# 01_DDR3L_256Mx32bits.net
KiCad netlist of a schematic drawn in Altium Designer
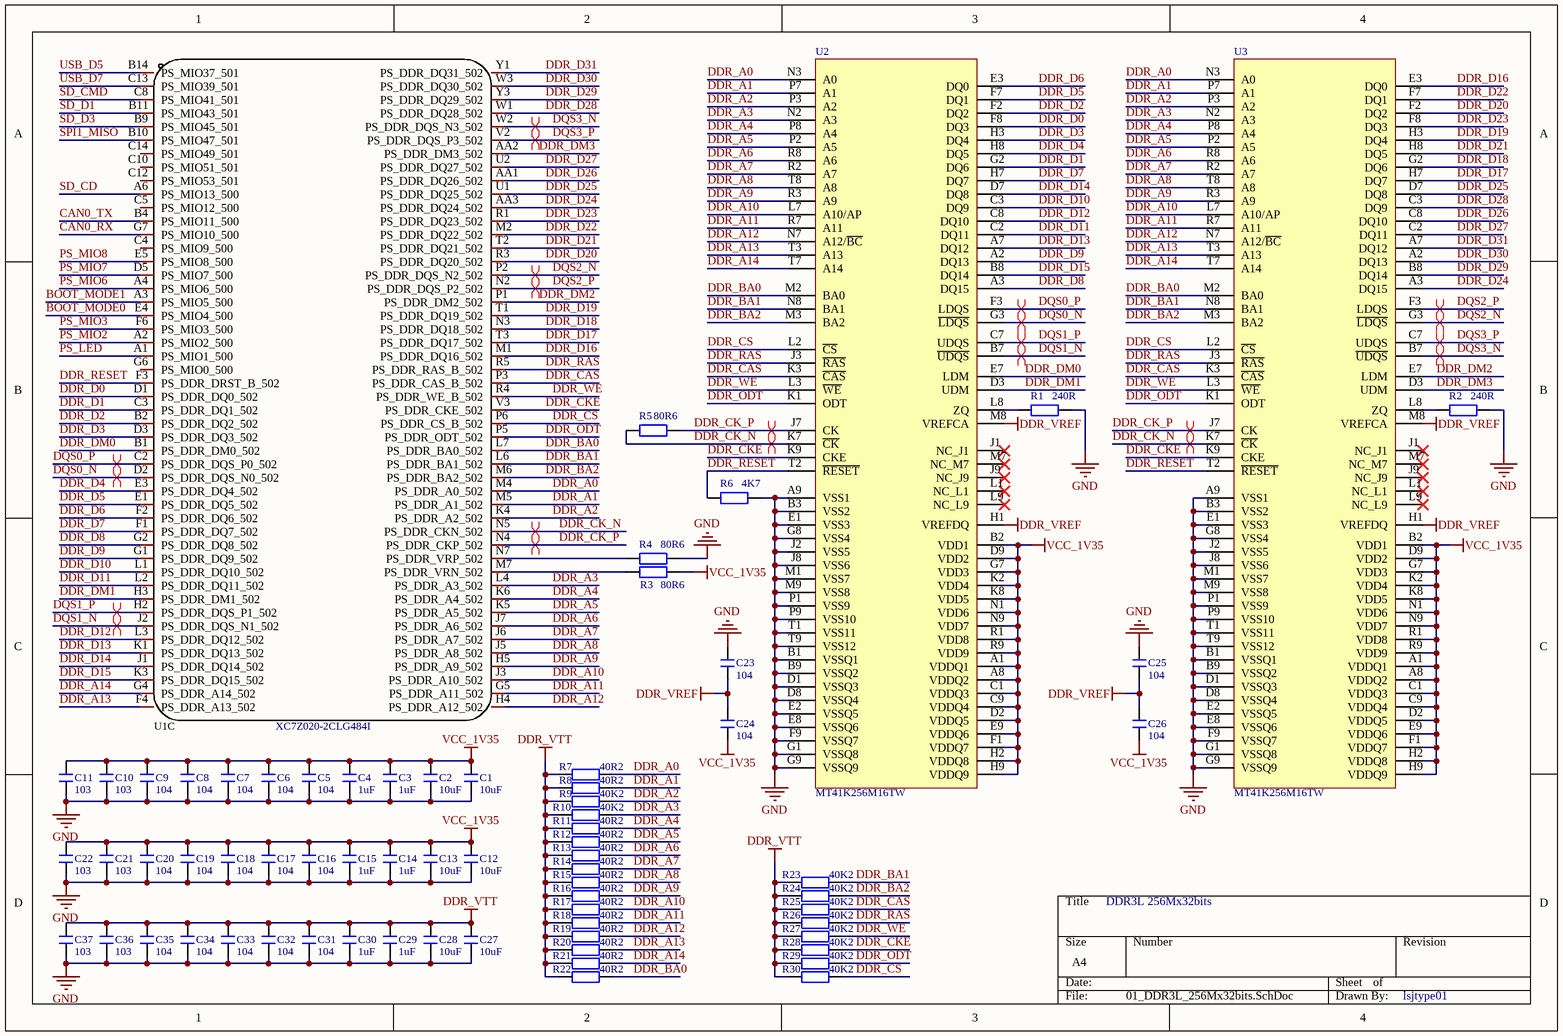
[diagram p0: 01_DDR3L_256Mx32bits.SchDoc]

(export (version "E")
  (design (tool "Eeschema 10.0.6"))
  (components
    (comp (ref "C1")
      (value "10uF")
      (footprint "C 0603")
      (description "无极性贴片电容")
      (fields (field (name "版权归属") "源创客"))
      (libsource (lib "STM32MP157核心板封装库V1.2") (part "C"))
    )
    (comp (ref "C2")
      (value "10uF")
      (footprint "C 0603")
      (description "无极性贴片电容")
      (fields (field (name "版权归属") "源创客"))
      (libsource (lib "STM32MP157核心板封装库V1.2") (part "C"))
    )
    (comp (ref "C3")
      (value "1uF")
      (footprint "C 0402")
      (description "无极性贴片电容")
      (fields (field (name "版权归属") "源创客"))
      (libsource (lib "STM32MP157核心板封装库V1.2") (part "C"))
    )
    (comp (ref "C4")
      (value "1uF")
      (footprint "C 0402")
      (description "无极性贴片电容")
      (fields (field (name "版权归属") "源创客"))
      (libsource (lib "STM32MP157核心板封装库V1.2") (part "C"))
    )
    (comp (ref "C5")
      (value "104")
      (footprint "C 0402")
      (description "无极性贴片电容")
      (fields (field (name "版权归属") "源创客"))
      (libsource (lib "STM32MP157核心板封装库V1.2") (part "C"))
    )
    (comp (ref "C6")
      (value "104")
      (footprint "C 0402")
      (description "无极性贴片电容")
      (fields (field (name "版权归属") "源创客"))
      (libsource (lib "STM32MP157核心板封装库V1.2") (part "C"))
    )
    (comp (ref "C7")
      (value "104")
      (footprint "C 0402")
      (description "无极性贴片电容")
      (fields (field (name "版权归属") "源创客"))
      (libsource (lib "STM32MP157核心板封装库V1.2") (part "C"))
    )
    (comp (ref "C8")
      (value "104")
      (footprint "C 0402")
      (description "无极性贴片电容")
      (fields (field (name "版权归属") "源创客"))
      (libsource (lib "STM32MP157核心板封装库V1.2") (part "C"))
    )
    (comp (ref "C9")
      (value "104")
      (footprint "C 0402")
      (description "无极性贴片电容")
      (fields (field (name "版权归属") "源创客"))
      (libsource (lib "STM32MP157核心板封装库V1.2") (part "C"))
    )
    (comp (ref "C10")
      (value "103")
      (footprint "C 0402")
      (description "无极性贴片电容")
      (fields (field (name "版权归属") "源创客"))
      (libsource (lib "STM32MP157核心板封装库V1.2") (part "C"))
    )
    (comp (ref "C11")
      (value "103")
      (footprint "C 0402")
      (description "无极性贴片电容")
      (fields (field (name "版权归属") "源创客"))
      (libsource (lib "STM32MP157核心板封装库V1.2") (part "C"))
    )
    (comp (ref "C12")
      (value "10uF")
      (footprint "C 0603")
      (description "无极性贴片电容")
      (fields (field (name "版权归属") "源创客"))
      (libsource (lib "STM32MP157核心板封装库V1.2") (part "C"))
    )
    (comp (ref "C13")
      (value "10uF")
      (footprint "C 0603")
      (description "无极性贴片电容")
      (fields (field (name "版权归属") "源创客"))
      (libsource (lib "STM32MP157核心板封装库V1.2") (part "C"))
    )
    (comp (ref "C14")
      (value "1uF")
      (footprint "C 0402")
      (description "无极性贴片电容")
      (fields (field (name "版权归属") "源创客"))
      (libsource (lib "STM32MP157核心板封装库V1.2") (part "C"))
    )
    (comp (ref "C15")
      (value "1uF")
      (footprint "C 0402")
      (description "无极性贴片电容")
      (fields (field (name "版权归属") "源创客"))
      (libsource (lib "STM32MP157核心板封装库V1.2") (part "C"))
    )
    (comp (ref "C16")
      (value "104")
      (footprint "C 0402")
      (description "无极性贴片电容")
      (fields (field (name "版权归属") "源创客"))
      (libsource (lib "STM32MP157核心板封装库V1.2") (part "C"))
    )
    (comp (ref "C17")
      (value "104")
      (footprint "C 0402")
      (description "无极性贴片电容")
      (fields (field (name "版权归属") "源创客"))
      (libsource (lib "STM32MP157核心板封装库V1.2") (part "C"))
    )
    (comp (ref "C18")
      (value "104")
      (footprint "C 0402")
      (description "无极性贴片电容")
      (fields (field (name "版权归属") "源创客"))
      (libsource (lib "STM32MP157核心板封装库V1.2") (part "C"))
    )
    (comp (ref "C19")
      (value "104")
      (footprint "C 0402")
      (description "无极性贴片电容")
      (fields (field (name "版权归属") "源创客"))
      (libsource (lib "STM32MP157核心板封装库V1.2") (part "C"))
    )
    (comp (ref "C20")
      (value "104")
      (footprint "C 0402")
      (description "无极性贴片电容")
      (fields (field (name "版权归属") "源创客"))
      (libsource (lib "STM32MP157核心板封装库V1.2") (part "C"))
    )
    (comp (ref "C21")
      (value "103")
      (footprint "C 0402")
      (description "无极性贴片电容")
      (fields (field (name "版权归属") "源创客"))
      (libsource (lib "STM32MP157核心板封装库V1.2") (part "C"))
    )
    (comp (ref "C22")
      (value "103")
      (footprint "C 0402")
      (description "无极性贴片电容")
      (fields (field (name "版权归属") "源创客"))
      (libsource (lib "STM32MP157核心板封装库V1.2") (part "C"))
    )
    (comp (ref "C23")
      (value "104")
      (footprint "C 0402")
      (description "无极性贴片电容")
      (fields (field (name "版权归属") "源创客"))
      (libsource (lib "STM32MP157核心板封装库V1.2") (part "C"))
    )
    (comp (ref "C24")
      (value "104")
      (footprint "C 0402")
      (description "无极性贴片电容")
      (fields (field (name "版权归属") "源创客"))
      (libsource (lib "STM32MP157核心板封装库V1.2") (part "C"))
    )
    (comp (ref "C25")
      (value "104")
      (footprint "C 0402")
      (description "无极性贴片电容")
      (fields (field (name "版权归属") "源创客"))
      (libsource (lib "STM32MP157核心板封装库V1.2") (part "C"))
    )
    (comp (ref "C26")
      (value "104")
      (footprint "C 0402")
      (description "无极性贴片电容")
      (fields (field (name "版权归属") "源创客"))
      (libsource (lib "STM32MP157核心板封装库V1.2") (part "C"))
    )
    (comp (ref "C27")
      (value "10uF")
      (footprint "C 0603")
      (description "无极性贴片电容")
      (fields (field (name "版权归属") "源创客"))
      (libsource (lib "STM32MP157核心板封装库V1.2") (part "C"))
    )
    (comp (ref "C28")
      (value "10uF")
      (footprint "C 0603")
      (description "无极性贴片电容")
      (fields (field (name "版权归属") "源创客"))
      (libsource (lib "STM32MP157核心板封装库V1.2") (part "C"))
    )
    (comp (ref "C29")
      (value "1uF")
      (footprint "C 0402")
      (description "无极性贴片电容")
      (fields (field (name "版权归属") "源创客"))
      (libsource (lib "STM32MP157核心板封装库V1.2") (part "C"))
    )
    (comp (ref "C30")
      (value "1uF")
      (footprint "C 0402")
      (description "无极性贴片电容")
      (fields (field (name "版权归属") "源创客"))
      (libsource (lib "STM32MP157核心板封装库V1.2") (part "C"))
    )
    (comp (ref "C31")
      (value "104")
      (footprint "C 0402")
      (description "无极性贴片电容")
      (fields (field (name "版权归属") "源创客"))
      (libsource (lib "STM32MP157核心板封装库V1.2") (part "C"))
    )
    (comp (ref "C32")
      (value "104")
      (footprint "C 0402")
      (description "无极性贴片电容")
      (fields (field (name "版权归属") "源创客"))
      (libsource (lib "STM32MP157核心板封装库V1.2") (part "C"))
    )
    (comp (ref "C33")
      (value "104")
      (footprint "C 0402")
      (description "无极性贴片电容")
      (fields (field (name "版权归属") "源创客"))
      (libsource (lib "STM32MP157核心板封装库V1.2") (part "C"))
    )
    (comp (ref "C34")
      (value "104")
      (footprint "C 0402")
      (description "无极性贴片电容")
      (fields (field (name "版权归属") "源创客"))
      (libsource (lib "STM32MP157核心板封装库V1.2") (part "C"))
    )
    (comp (ref "C35")
      (value "104")
      (footprint "C 0402")
      (description "无极性贴片电容")
      (fields (field (name "版权归属") "源创客"))
      (libsource (lib "STM32MP157核心板封装库V1.2") (part "C"))
    )
    (comp (ref "C36")
      (value "103")
      (footprint "C 0402")
      (description "无极性贴片电容")
      (fields (field (name "版权归属") "源创客"))
      (libsource (lib "STM32MP157核心板封装库V1.2") (part "C"))
    )
    (comp (ref "C37")
      (value "103")
      (footprint "C 0402")
      (description "无极性贴片电容")
      (fields (field (name "版权归属") "源创客"))
      (libsource (lib "STM32MP157核心板封装库V1.2") (part "C"))
    )
    (comp (ref "R1")
      (value "240R")
      (footprint "R 0402")
      (description "贴片电阻")
      (fields (field (name "版权归属") "源创客"))
      (libsource (lib "STM32MP157核心板封装库V1.2") (part "R"))
    )
    (comp (ref "R2")
      (value "240R")
      (footprint "R 0402")
      (description "贴片电阻")
      (fields (field (name "版权归属") "源创客"))
      (libsource (lib "STM32MP157核心板封装库V1.2") (part "R"))
    )
    (comp (ref "R3")
      (value "80R6")
      (footprint "R 0402")
      (description "贴片电阻")
      (fields (field (name "版权归属") "源创客"))
      (libsource (lib "STM32MP157核心板封装库V1.2") (part "R"))
    )
    (comp (ref "R4")
      (value "80R6")
      (footprint "R 0402")
      (description "贴片电阻")
      (fields (field (name "版权归属") "源创客"))
      (libsource (lib "STM32MP157核心板封装库V1.2") (part "R"))
    )
    (comp (ref "R5")
      (value "80R6")
      (footprint "R 0402")
      (description "贴片电阻")
      (fields (field (name "版权归属") "源创客"))
      (libsource (lib "STM32MP157核心板封装库V1.2") (part "R"))
    )
    (comp (ref "R6")
      (value "4K7")
      (footprint "R 0402")
      (description "贴片电阻")
      (fields (field (name "版权归属") "源创客"))
      (libsource (lib "STM32MP157核心板封装库V1.2") (part "R"))
    )
    (comp (ref "R7")
      (value "40R2")
      (footprint "R 0402")
      (description "贴片电阻")
      (fields (field (name "版权归属") "源创客"))
      (libsource (lib "STM32MP157核心板封装库V1.2") (part "R"))
    )
    (comp (ref "R8")
      (value "40R2")
      (footprint "R 0402")
      (description "贴片电阻")
      (fields (field (name "版权归属") "源创客"))
      (libsource (lib "STM32MP157核心板封装库V1.2") (part "R"))
    )
    (comp (ref "R9")
      (value "40K2")
      (footprint "R 0402")
      (description "贴片电阻")
      (fields (field (name "版权归属") "源创客"))
      (libsource (lib "STM32MP157核心板封装库V1.2") (part "R"))
    )
    (comp (ref "R10")
      (value "40K2")
      (footprint "R 0402")
      (description "贴片电阻")
      (fields (field (name "版权归属") "源创客"))
      (libsource (lib "STM32MP157核心板封装库V1.2") (part "R"))
    )
    (comp (ref "R11")
      (value "40R2")
      (footprint "R 0402")
      (description "贴片电阻")
      (fields (field (name "版权归属") "源创客"))
      (libsource (lib "STM32MP157核心板封装库V1.2") (part "R"))
    )
    (comp (ref "R12")
      (value "40R2")
      (footprint "R 0402")
      (description "贴片电阻")
      (fields (field (name "版权归属") "源创客"))
      (libsource (lib "STM32MP157核心板封装库V1.2") (part "R"))
    )
    (comp (ref "R13")
      (value "40R2")
      (footprint "R 0402")
      (description "贴片电阻")
      (fields (field (name "版权归属") "源创客"))
      (libsource (lib "STM32MP157核心板封装库V1.2") (part "R"))
    )
    (comp (ref "R14")
      (value "40R2")
      (footprint "R 0402")
      (description "贴片电阻")
      (fields (field (name "版权归属") "源创客"))
      (libsource (lib "STM32MP157核心板封装库V1.2") (part "R"))
    )
    (comp (ref "R15")
      (value "40R2")
      (footprint "R 0402")
      (description "贴片电阻")
      (fields (field (name "版权归属") "源创客"))
      (libsource (lib "STM32MP157核心板封装库V1.2") (part "R"))
    )
    (comp (ref "R16")
      (value "40R2")
      (footprint "R 0402")
      (description "贴片电阻")
      (fields (field (name "版权归属") "源创客"))
      (libsource (lib "STM32MP157核心板封装库V1.2") (part "R"))
    )
    (comp (ref "R17")
      (value "40R2")
      (footprint "R 0402")
      (description "贴片电阻")
      (fields (field (name "版权归属") "源创客"))
      (libsource (lib "STM32MP157核心板封装库V1.2") (part "R"))
    )
    (comp (ref "R18")
      (value "40R2")
      (footprint "R 0402")
      (description "贴片电阻")
      (fields (field (name "版权归属") "源创客"))
      (libsource (lib "STM32MP157核心板封装库V1.2") (part "R"))
    )
    (comp (ref "R19")
      (value "40R2")
      (footprint "R 0402")
      (description "贴片电阻")
      (fields (field (name "版权归属") "源创客"))
      (libsource (lib "STM32MP157核心板封装库V1.2") (part "R"))
    )
    (comp (ref "R20")
      (value "40R2")
      (footprint "R 0402")
      (description "贴片电阻")
      (fields (field (name "版权归属") "源创客"))
      (libsource (lib "STM32MP157核心板封装库V1.2") (part "R"))
    )
    (comp (ref "R21")
      (value "40R2")
      (footprint "R 0402")
      (description "贴片电阻")
      (fields (field (name "版权归属") "源创客"))
      (libsource (lib "STM32MP157核心板封装库V1.2") (part "R"))
    )
    (comp (ref "R22")
      (value "40R2")
      (footprint "R 0402")
      (description "贴片电阻")
      (fields (field (name "版权归属") "源创客"))
      (libsource (lib "STM32MP157核心板封装库V1.2") (part "R"))
    )
    (comp (ref "R23")
      (value "40K2")
      (footprint "R 0402")
      (description "贴片电阻")
      (fields (field (name "版权归属") "源创客"))
      (libsource (lib "STM32MP157核心板封装库V1.2") (part "R"))
    )
    (comp (ref "R24")
      (value "40K2")
      (footprint "R 0402")
      (description "贴片电阻")
      (fields (field (name "版权归属") "源创客"))
      (libsource (lib "STM32MP157核心板封装库V1.2") (part "R"))
    )
    (comp (ref "R25")
      (value "40K2")
      (footprint "R 0402")
      (description "贴片电阻")
      (fields (field (name "版权归属") "源创客"))
      (libsource (lib "STM32MP157核心板封装库V1.2") (part "R"))
    )
    (comp (ref "R26")
      (value "40K2")
      (footprint "R 0402")
      (description "贴片电阻")
      (fields (field (name "版权归属") "源创客"))
      (libsource (lib "STM32MP157核心板封装库V1.2") (part "R"))
    )
    (comp (ref "R27")
      (value "40K2")
      (footprint "R 0402")
      (description "贴片电阻")
      (fields (field (name "版权归属") "源创客"))
      (libsource (lib "STM32MP157核心板封装库V1.2") (part "R"))
    )
    (comp (ref "R28")
      (value "40K2")
      (footprint "R 0402")
      (description "贴片电阻")
      (fields (field (name "版权归属") "源创客"))
      (libsource (lib "STM32MP157核心板封装库V1.2") (part "R"))
    )
    (comp (ref "R29")
      (value "40K2")
      (footprint "R 0402")
      (description "贴片电阻")
      (fields (field (name "版权归属") "源创客"))
      (libsource (lib "STM32MP157核心板封装库V1.2") (part "R"))
    )
    (comp (ref "R30")
      (value "40K2")
      (footprint "R 0402")
      (description "贴片电阻")
      (fields (field (name "版权归属") "源创客"))
      (libsource (lib "STM32MP157核心板封装库V1.2") (part "R"))
    )
    (comp (ref "U1")
      (value "XC7Z020-2CLG484I")
      (footprint "CSPBGA-484")
      (fields (field (name "MANUFACTURER") "XILINX(赛灵思)"))
      (libsource (lib "XC7Z020-2CLG484I1") (part "XC7Z020-2CLG484I"))
    )
    (comp (ref "U2")
      (value "MT41K256M16TW")
      (footprint "FBGA_96")
      (libsource (lib "STM32MP157核心板封装库V1.2") (part "MT41K256M16TW"))
    )
    (comp (ref "U3")
      (value "MT41K256M16TW")
      (footprint "FBGA_96")
      (libsource (lib "STM32MP157核心板封装库V1.2") (part "MT41K256M16TW"))
    )
  )
  (nets
    (net (code "1") (name "/BOOT_MODE0") (class "Default")
      (node (ref "U1") (pin "E4") (pinfunction "PS_MIO4_500_E4") (pintype "passive"))
    )
    (net (code "2") (name "/BOOT_MODE1") (class "Default")
      (node (ref "U1") (pin "A3") (pinfunction "PS_MIO5_500_A3") (pintype "passive"))
    )
    (net (code "3") (name "/CAN0_RX") (class "Default")
      (node (ref "U1") (pin "G7") (pinfunction "PS_MIO10_500_G7") (pintype "passive"))
    )
    (net (code "4") (name "/CAN0_TX") (class "Default")
      (node (ref "U1") (pin "B4") (pinfunction "PS_MIO11_500_B4") (pintype "passive"))
    )
    (net (code "5") (name "/DDR_A0") (class "Default")
      (node (ref "R7") (pin "2") (pinfunction "2_2") (pintype "passive"))
      (node (ref "U1") (pin "M4") (pinfunction "PS_DDR_A0_502_M4") (pintype "passive"))
      (node (ref "U2") (pin "N3") (pinfunction "A0_N3") (pintype "passive"))
      (node (ref "U3") (pin "N3") (pinfunction "A0_N3") (pintype "passive"))
    )
    (net (code "6") (name "/DDR_A1") (class "Default")
      (node (ref "R8") (pin "2") (pinfunction "2_2") (pintype "passive"))
      (node (ref "U1") (pin "M5") (pinfunction "PS_DDR_A1_502_M5") (pintype "passive"))
      (node (ref "U2") (pin "P7") (pinfunction "A1_P7") (pintype "passive"))
      (node (ref "U3") (pin "P7") (pinfunction "A1_P7") (pintype "passive"))
    )
    (net (code "7") (name "/DDR_A2") (class "Default")
      (node (ref "R9") (pin "2") (pinfunction "2_2") (pintype "passive"))
      (node (ref "U1") (pin "K4") (pinfunction "PS_DDR_A2_502_K4") (pintype "passive"))
      (node (ref "U2") (pin "P3") (pinfunction "A2_P3") (pintype "passive"))
      (node (ref "U3") (pin "P3") (pinfunction "A2_P3") (pintype "passive"))
    )
    (net (code "8") (name "/DDR_A3") (class "Default")
      (node (ref "R10") (pin "2") (pinfunction "2_2") (pintype "passive"))
      (node (ref "U1") (pin "L4") (pinfunction "PS_DDR_A3_502_L4") (pintype "passive"))
      (node (ref "U2") (pin "N2") (pinfunction "A3_N2") (pintype "passive"))
      (node (ref "U3") (pin "N2") (pinfunction "A3_N2") (pintype "passive"))
    )
    (net (code "9") (name "/DDR_A4") (class "Default")
      (node (ref "R11") (pin "2") (pinfunction "2_2") (pintype "passive"))
      (node (ref "U1") (pin "K6") (pinfunction "PS_DDR_A4_502_K6") (pintype "passive"))
      (node (ref "U2") (pin "P8") (pinfunction "A4_P8") (pintype "passive"))
      (node (ref "U3") (pin "P8") (pinfunction "A4_P8") (pintype "passive"))
    )
    (net (code "10") (name "/DDR_A5") (class "Default")
      (node (ref "R12") (pin "2") (pinfunction "2_2") (pintype "passive"))
      (node (ref "U1") (pin "K5") (pinfunction "PS_DDR_A5_502_K5") (pintype "passive"))
      (node (ref "U2") (pin "P2") (pinfunction "A5_P2") (pintype "passive"))
      (node (ref "U3") (pin "P2") (pinfunction "A5_P2") (pintype "passive"))
    )
    (net (code "11") (name "/DDR_A6") (class "Default")
      (node (ref "R13") (pin "2") (pinfunction "2_2") (pintype "passive"))
      (node (ref "U1") (pin "J7") (pinfunction "PS_DDR_A6_502_J7") (pintype "passive"))
      (node (ref "U2") (pin "R8") (pinfunction "A6_R8") (pintype "passive"))
      (node (ref "U3") (pin "R8") (pinfunction "A6_R8") (pintype "passive"))
    )
    (net (code "12") (name "/DDR_A7") (class "Default")
      (node (ref "R14") (pin "2") (pinfunction "2_2") (pintype "passive"))
      (node (ref "U1") (pin "J6") (pinfunction "PS_DDR_A7_502_J6") (pintype "passive"))
      (node (ref "U2") (pin "R2") (pinfunction "A7_R2") (pintype "passive"))
      (node (ref "U3") (pin "R2") (pinfunction "A7_R2") (pintype "passive"))
    )
    (net (code "13") (name "/DDR_A8") (class "Default")
      (node (ref "R15") (pin "2") (pinfunction "2_2") (pintype "passive"))
      (node (ref "U1") (pin "J5") (pinfunction "PS_DDR_A8_502_J5") (pintype "passive"))
      (node (ref "U2") (pin "T8") (pinfunction "A8_T8") (pintype "passive"))
      (node (ref "U3") (pin "T8") (pinfunction "A8_T8") (pintype "passive"))
    )
    (net (code "14") (name "/DDR_A9") (class "Default")
      (node (ref "R16") (pin "2") (pinfunction "2_2") (pintype "passive"))
      (node (ref "U1") (pin "H5") (pinfunction "PS_DDR_A9_502_H5") (pintype "passive"))
      (node (ref "U2") (pin "R3") (pinfunction "A9_R3") (pintype "passive"))
      (node (ref "U3") (pin "R3") (pinfunction "A9_R3") (pintype "passive"))
    )
    (net (code "15") (name "/DDR_A10") (class "Default")
      (node (ref "R17") (pin "2") (pinfunction "2_2") (pintype "passive"))
      (node (ref "U1") (pin "J3") (pinfunction "PS_DDR_A10_502_J3") (pintype "passive"))
      (node (ref "U2") (pin "L7") (pinfunction "A10/AP_L7") (pintype "passive"))
      (node (ref "U3") (pin "L7") (pinfunction "A10/AP_L7") (pintype "passive"))
    )
    (net (code "16") (name "/DDR_A11") (class "Default")
      (node (ref "R18") (pin "2") (pinfunction "2_2") (pintype "passive"))
      (node (ref "U1") (pin "G5") (pinfunction "PS_DDR_A11_502_G5") (pintype "passive"))
      (node (ref "U2") (pin "R7") (pinfunction "A11_R7") (pintype "passive"))
      (node (ref "U3") (pin "R7") (pinfunction "A11_R7") (pintype "passive"))
    )
    (net (code "17") (name "/DDR_A12") (class "Default")
      (node (ref "R19") (pin "2") (pinfunction "2_2") (pintype "passive"))
      (node (ref "U1") (pin "H4") (pinfunction "PS_DDR_A12_502_H4") (pintype "passive"))
      (node (ref "U2") (pin "N7") (pinfunction "A12/~{BC}_N7") (pintype "passive"))
      (node (ref "U3") (pin "N7") (pinfunction "A12/~{BC}_N7") (pintype "passive"))
    )
    (net (code "18") (name "/DDR_A13") (class "Default")
      (node (ref "R20") (pin "2") (pinfunction "2_2") (pintype "passive"))
      (node (ref "U1") (pin "F4") (pinfunction "PS_DDR_A13_502_F4") (pintype "passive"))
      (node (ref "U2") (pin "T3") (pinfunction "A13_T3") (pintype "passive"))
      (node (ref "U3") (pin "T3") (pinfunction "A13_T3") (pintype "passive"))
    )
    (net (code "19") (name "/DDR_A14") (class "Default")
      (node (ref "R21") (pin "2") (pinfunction "2_2") (pintype "passive"))
      (node (ref "U1") (pin "G4") (pinfunction "PS_DDR_A14_502_G4") (pintype "passive"))
      (node (ref "U2") (pin "T7") (pinfunction "A14_T7") (pintype "passive"))
      (node (ref "U3") (pin "T7") (pinfunction "A14_T7") (pintype "passive"))
    )
    (net (code "20") (name "/DDR_BA0") (class "Default")
      (node (ref "R22") (pin "2") (pinfunction "2_2") (pintype "passive"))
      (node (ref "U1") (pin "L7") (pinfunction "PS_DDR_BA0_502_L7") (pintype "passive"))
      (node (ref "U2") (pin "M2") (pinfunction "BA0_M2") (pintype "passive"))
      (node (ref "U3") (pin "M2") (pinfunction "BA0_M2") (pintype "passive"))
    )
    (net (code "21") (name "/DDR_BA1") (class "Default")
      (node (ref "R23") (pin "2") (pinfunction "2_2") (pintype "passive"))
      (node (ref "U1") (pin "L6") (pinfunction "PS_DDR_BA1_502_L6") (pintype "passive"))
      (node (ref "U2") (pin "N8") (pinfunction "BA1_N8") (pintype "passive"))
      (node (ref "U3") (pin "N8") (pinfunction "BA1_N8") (pintype "passive"))
    )
    (net (code "22") (name "/DDR_BA2") (class "Default")
      (node (ref "R24") (pin "2") (pinfunction "2_2") (pintype "passive"))
      (node (ref "U1") (pin "M6") (pinfunction "PS_DDR_BA2_502_M6") (pintype "passive"))
      (node (ref "U2") (pin "M3") (pinfunction "BA2_M3") (pintype "passive"))
      (node (ref "U3") (pin "M3") (pinfunction "BA2_M3") (pintype "passive"))
    )
    (net (code "23") (name "/DDR_CAS") (class "Default")
      (node (ref "R25") (pin "2") (pinfunction "2_2") (pintype "passive"))
      (node (ref "U1") (pin "P3") (pinfunction "PS_DDR_CAS_B_502_P3") (pintype "passive"))
      (node (ref "U2") (pin "K3") (pinfunction "~{CAS}_K3") (pintype "passive"))
      (node (ref "U3") (pin "K3") (pinfunction "~{CAS}_K3") (pintype "passive"))
    )
    (net (code "24") (name "/DDR_CKE") (class "Default")
      (node (ref "R28") (pin "2") (pinfunction "2_2") (pintype "passive"))
      (node (ref "U1") (pin "V3") (pinfunction "PS_DDR_CKE_502_V3") (pintype "passive"))
      (node (ref "U2") (pin "K9") (pinfunction "CKE_K9") (pintype "passive"))
      (node (ref "U3") (pin "K9") (pinfunction "CKE_K9") (pintype "passive"))
    )
    (net (code "25") (name "/DDR_CK_N") (class "Default")
      (node (ref "R5") (pin "2") (pinfunction "2_2") (pintype "passive"))
      (node (ref "U1") (pin "N5") (pinfunction "PS_DDR_CKN_502_N5") (pintype "passive"))
      (node (ref "U2") (pin "K7") (pinfunction "~{CK}_K7") (pintype "passive"))
      (node (ref "U3") (pin "K7") (pinfunction "~{CK}_K7") (pintype "passive"))
    )
    (net (code "26") (name "/DDR_CK_P") (class "Default")
      (node (ref "R5") (pin "1") (pinfunction "1_1") (pintype "passive"))
      (node (ref "U1") (pin "N4") (pinfunction "PS_DDR_CKP_502_N4") (pintype "passive"))
      (node (ref "U2") (pin "J7") (pinfunction "CK_J7") (pintype "passive"))
      (node (ref "U3") (pin "J7") (pinfunction "CK_J7") (pintype "passive"))
    )
    (net (code "27") (name "/DDR_CS") (class "Default")
      (node (ref "R30") (pin "2") (pinfunction "2_2") (pintype "passive"))
      (node (ref "U1") (pin "P6") (pinfunction "PS_DDR_CS_B_502_P6") (pintype "passive"))
      (node (ref "U2") (pin "L2") (pinfunction "~{CS}_L2") (pintype "passive"))
      (node (ref "U3") (pin "L2") (pinfunction "~{CS}_L2") (pintype "passive"))
    )
    (net (code "28") (name "/DDR_D0") (class "Default")
      (node (ref "U1") (pin "D1") (pinfunction "PS_DDR_DQ0_502_D1") (pintype "passive"))
      (node (ref "U2") (pin "F8") (pinfunction "DQ3_F8") (pintype "passive"))
    )
    (net (code "29") (name "/DDR_D1") (class "Default")
      (node (ref "U1") (pin "C3") (pinfunction "PS_DDR_DQ1_502_C3") (pintype "passive"))
      (node (ref "U2") (pin "G2") (pinfunction "DQ6_G2") (pintype "passive"))
    )
    (net (code "30") (name "/DDR_D2") (class "Default")
      (node (ref "U1") (pin "B2") (pinfunction "PS_DDR_DQ2_502_B2") (pintype "passive"))
      (node (ref "U2") (pin "F2") (pinfunction "DQ2_F2") (pintype "passive"))
    )
    (net (code "31") (name "/DDR_D3") (class "Default")
      (node (ref "U1") (pin "D3") (pinfunction "PS_DDR_DQ3_502_D3") (pintype "passive"))
      (node (ref "U2") (pin "H3") (pinfunction "DQ4_H3") (pintype "passive"))
    )
    (net (code "32") (name "/DDR_D4") (class "Default")
      (node (ref "U1") (pin "E3") (pinfunction "PS_DDR_DQ4_502_E3") (pintype "passive"))
      (node (ref "U2") (pin "H8") (pinfunction "DQ5_H8") (pintype "passive"))
    )
    (net (code "33") (name "/DDR_D5") (class "Default")
      (node (ref "U1") (pin "E1") (pinfunction "PS_DDR_DQ5_502_E1") (pintype "passive"))
      (node (ref "U2") (pin "F7") (pinfunction "DQ1_F7") (pintype "passive"))
    )
    (net (code "34") (name "/DDR_D6") (class "Default")
      (node (ref "U1") (pin "F2") (pinfunction "PS_DDR_DQ6_502_F2") (pintype "passive"))
      (node (ref "U2") (pin "E3") (pinfunction "DQ0_E3") (pintype "passive"))
    )
    (net (code "35") (name "/DDR_D7") (class "Default")
      (node (ref "U1") (pin "F1") (pinfunction "PS_DDR_DQ7_502_F1") (pintype "passive"))
      (node (ref "U2") (pin "H7") (pinfunction "DQ7_H7") (pintype "passive"))
    )
    (net (code "36") (name "/DDR_D8") (class "Default")
      (node (ref "U1") (pin "G2") (pinfunction "PS_DDR_DQ8_502_G2") (pintype "passive"))
      (node (ref "U2") (pin "A3") (pinfunction "DQ15_A3") (pintype "passive"))
    )
    (net (code "37") (name "/DDR_D9") (class "Default")
      (node (ref "U1") (pin "G1") (pinfunction "PS_DDR_DQ9_502_G1") (pintype "passive"))
      (node (ref "U2") (pin "A2") (pinfunction "DQ13_A2") (pintype "passive"))
    )
    (net (code "38") (name "/DDR_D10") (class "Default")
      (node (ref "U1") (pin "L1") (pinfunction "PS_DDR_DQ10_502_L1") (pintype "passive"))
      (node (ref "U2") (pin "C3") (pinfunction "DQ9_C3") (pintype "passive"))
    )
    (net (code "39") (name "/DDR_D11") (class "Default")
      (node (ref "U1") (pin "L2") (pinfunction "PS_DDR_DQ11_502_L2") (pintype "passive"))
      (node (ref "U2") (pin "C2") (pinfunction "DQ11_C2") (pintype "passive"))
    )
    (net (code "40") (name "/DDR_D12") (class "Default")
      (node (ref "U1") (pin "L3") (pinfunction "PS_DDR_DQ12_502_L3") (pintype "passive"))
      (node (ref "U2") (pin "C8") (pinfunction "DQ10_C8") (pintype "passive"))
    )
    (net (code "41") (name "/DDR_D13") (class "Default")
      (node (ref "U1") (pin "K1") (pinfunction "PS_DDR_DQ13_502_K1") (pintype "passive"))
      (node (ref "U2") (pin "A7") (pinfunction "DQ12_A7") (pintype "passive"))
    )
    (net (code "42") (name "/DDR_D14") (class "Default")
      (node (ref "U1") (pin "J1") (pinfunction "PS_DDR_DQ14_502_J1") (pintype "passive"))
      (node (ref "U2") (pin "D7") (pinfunction "DQ8_D7") (pintype "passive"))
    )
    (net (code "43") (name "/DDR_D15") (class "Default")
      (node (ref "U1") (pin "K3") (pinfunction "PS_DDR_DQ15_502_K3") (pintype "passive"))
      (node (ref "U2") (pin "B8") (pinfunction "DQ14_B8") (pintype "passive"))
    )
    (net (code "44") (name "/DDR_D16") (class "Default")
      (node (ref "U1") (pin "M1") (pinfunction "PS_DDR_DQ16_502_M1") (pintype "passive"))
      (node (ref "U3") (pin "E3") (pinfunction "DQ0_E3") (pintype "passive"))
    )
    (net (code "45") (name "/DDR_D17") (class "Default")
      (node (ref "U1") (pin "T3") (pinfunction "PS_DDR_DQ17_502_T3") (pintype "passive"))
      (node (ref "U3") (pin "H7") (pinfunction "DQ7_H7") (pintype "passive"))
    )
    (net (code "46") (name "/DDR_D18") (class "Default")
      (node (ref "U1") (pin "N3") (pinfunction "PS_DDR_DQ18_502_N3") (pintype "passive"))
      (node (ref "U3") (pin "G2") (pinfunction "DQ6_G2") (pintype "passive"))
    )
    (net (code "47") (name "/DDR_D19") (class "Default")
      (node (ref "U1") (pin "T1") (pinfunction "PS_DDR_DQ19_502_T1") (pintype "passive"))
      (node (ref "U3") (pin "H3") (pinfunction "DQ4_H3") (pintype "passive"))
    )
    (net (code "48") (name "/DDR_D20") (class "Default")
      (node (ref "U1") (pin "R3") (pinfunction "PS_DDR_DQ20_502_R3") (pintype "passive"))
      (node (ref "U3") (pin "F2") (pinfunction "DQ2_F2") (pintype "passive"))
    )
    (net (code "49") (name "/DDR_D21") (class "Default")
      (node (ref "U1") (pin "T2") (pinfunction "PS_DDR_DQ21_502_T2") (pintype "passive"))
      (node (ref "U3") (pin "H8") (pinfunction "DQ5_H8") (pintype "passive"))
    )
    (net (code "50") (name "/DDR_D22") (class "Default")
      (node (ref "U1") (pin "M2") (pinfunction "PS_DDR_DQ22_502_M2") (pintype "passive"))
      (node (ref "U3") (pin "F7") (pinfunction "DQ1_F7") (pintype "passive"))
    )
    (net (code "51") (name "/DDR_D23") (class "Default")
      (node (ref "U1") (pin "R1") (pinfunction "PS_DDR_DQ23_502_R1") (pintype "passive"))
      (node (ref "U3") (pin "F8") (pinfunction "DQ3_F8") (pintype "passive"))
    )
    (net (code "52") (name "/DDR_D24") (class "Default")
      (node (ref "U1") (pin "AA3") (pinfunction "PS_DDR_DQ24_502_AA3") (pintype "passive"))
      (node (ref "U3") (pin "A3") (pinfunction "DQ15_A3") (pintype "passive"))
    )
    (net (code "53") (name "/DDR_D25") (class "Default")
      (node (ref "U1") (pin "U1") (pinfunction "PS_DDR_DQ25_502_U1") (pintype "passive"))
      (node (ref "U3") (pin "D7") (pinfunction "DQ8_D7") (pintype "passive"))
    )
    (net (code "54") (name "/DDR_D26") (class "Default")
      (node (ref "U1") (pin "AA1") (pinfunction "PS_DDR_DQ26_502_AA1") (pintype "passive"))
      (node (ref "U3") (pin "C8") (pinfunction "DQ10_C8") (pintype "passive"))
    )
    (net (code "55") (name "/DDR_D27") (class "Default")
      (node (ref "U1") (pin "U2") (pinfunction "PS_DDR_DQ27_502_U2") (pintype "passive"))
      (node (ref "U3") (pin "C2") (pinfunction "DQ11_C2") (pintype "passive"))
    )
    (net (code "56") (name "/DDR_D28") (class "Default")
      (node (ref "U1") (pin "W1") (pinfunction "PS_DDR_DQ28_502_W1") (pintype "passive"))
      (node (ref "U3") (pin "C3") (pinfunction "DQ9_C3") (pintype "passive"))
    )
    (net (code "57") (name "/DDR_D29") (class "Default")
      (node (ref "U1") (pin "Y3") (pinfunction "PS_DDR_DQ29_502_Y3") (pintype "passive"))
      (node (ref "U3") (pin "B8") (pinfunction "DQ14_B8") (pintype "passive"))
    )
    (net (code "58") (name "/DDR_D30") (class "Default")
      (node (ref "U1") (pin "W3") (pinfunction "PS_DDR_DQ30_502_W3") (pintype "passive"))
      (node (ref "U3") (pin "A2") (pinfunction "DQ13_A2") (pintype "passive"))
    )
    (net (code "59") (name "/DDR_D31") (class "Default")
      (node (ref "U1") (pin "Y1") (pinfunction "PS_DDR_DQ31_502_Y1") (pintype "passive"))
      (node (ref "U3") (pin "A7") (pinfunction "DQ12_A7") (pintype "passive"))
    )
    (net (code "60") (name "/DDR_DM0") (class "Default")
      (node (ref "U1") (pin "B1") (pinfunction "PS_DDR_DM0_502_B1") (pintype "passive"))
      (node (ref "U2") (pin "E7") (pinfunction "LDM_E7") (pintype "passive"))
    )
    (net (code "61") (name "/DDR_DM1") (class "Default")
      (node (ref "U1") (pin "H3") (pinfunction "PS_DDR_DM1_502_H3") (pintype "passive"))
      (node (ref "U2") (pin "D3") (pinfunction "UDM_D3") (pintype "passive"))
    )
    (net (code "62") (name "/DDR_DM2") (class "Default")
      (node (ref "U1") (pin "P1") (pinfunction "PS_DDR_DM2_502_P1") (pintype "passive"))
      (node (ref "U3") (pin "E7") (pinfunction "LDM_E7") (pintype "passive"))
    )
    (net (code "63") (name "/DDR_DM3") (class "Default")
      (node (ref "U1") (pin "AA2") (pinfunction "PS_DDR_DM3_502_AA2") (pintype "passive"))
      (node (ref "U3") (pin "D3") (pinfunction "UDM_D3") (pintype "passive"))
    )
    (net (code "64") (name "/DDR_ODT") (class "Default")
      (node (ref "R29") (pin "2") (pinfunction "2_2") (pintype "passive"))
      (node (ref "U1") (pin "P5") (pinfunction "PS_DDR_ODT_502_P5") (pintype "passive"))
      (node (ref "U2") (pin "K1") (pinfunction "ODT_K1") (pintype "passive"))
      (node (ref "U3") (pin "K1") (pinfunction "ODT_K1") (pintype "passive"))
    )
    (net (code "65") (name "/DDR_RAS") (class "Default")
      (node (ref "R26") (pin "2") (pinfunction "2_2") (pintype "passive"))
      (node (ref "U1") (pin "R5") (pinfunction "PS_DDR_RAS_B_502_R5") (pintype "passive"))
      (node (ref "U2") (pin "J3") (pinfunction "~{RAS}_J3") (pintype "passive"))
      (node (ref "U3") (pin "J3") (pinfunction "~{RAS}_J3") (pintype "passive"))
    )
    (net (code "66") (name "/DDR_RESET") (class "Default")
      (node (ref "R6") (pin "2") (pinfunction "2_2") (pintype "passive"))
      (node (ref "U1") (pin "F3") (pinfunction "PS_DDR_DRST_B_502_F3") (pintype "passive"))
      (node (ref "U2") (pin "T2") (pinfunction "~{RESET}_T2") (pintype "passive"))
      (node (ref "U3") (pin "T2") (pinfunction "~{RESET}_T2") (pintype "passive"))
    )
    (net (code "67") (name "/DDR_WE") (class "Default")
      (node (ref "R27") (pin "2") (pinfunction "2_2") (pintype "passive"))
      (node (ref "U1") (pin "R4") (pinfunction "PS_DDR_WE_B_502_R4") (pintype "passive"))
      (node (ref "U2") (pin "L3") (pinfunction "~{WE}_L3") (pintype "passive"))
      (node (ref "U3") (pin "L3") (pinfunction "~{WE}_L3") (pintype "passive"))
    )
    (net (code "68") (name "/DQS0_N") (class "Default")
      (node (ref "U1") (pin "D2") (pinfunction "PS_DDR_DQS_N0_502_D2") (pintype "passive"))
      (node (ref "U2") (pin "G3") (pinfunction "~{LDQS}_G3") (pintype "passive"))
    )
    (net (code "69") (name "/DQS0_P") (class "Default")
      (node (ref "U1") (pin "C2") (pinfunction "PS_DDR_DQS_P0_502_C2") (pintype "passive"))
      (node (ref "U2") (pin "F3") (pinfunction "LDQS_F3") (pintype "passive"))
    )
    (net (code "70") (name "/DQS1_N") (class "Default")
      (node (ref "U1") (pin "J2") (pinfunction "PS_DDR_DQS_N1_502_J2") (pintype "passive"))
      (node (ref "U2") (pin "B7") (pinfunction "~{UDQS}_B7") (pintype "passive"))
    )
    (net (code "71") (name "/DQS1_P") (class "Default")
      (node (ref "U1") (pin "H2") (pinfunction "PS_DDR_DQS_P1_502_H2") (pintype "passive"))
      (node (ref "U2") (pin "C7") (pinfunction "UDQS_C7") (pintype "passive"))
    )
    (net (code "72") (name "/DQS2_N") (class "Default")
      (node (ref "U1") (pin "P2") (pinfunction "PS_DDR_DQS_N2_502_P2") (pintype "passive"))
      (node (ref "U3") (pin "G3") (pinfunction "~{LDQS}_G3") (pintype "passive"))
    )
    (net (code "73") (name "/DQS2_P") (class "Default")
      (node (ref "U1") (pin "N2") (pinfunction "PS_DDR_DQS_P2_502_N2") (pintype "passive"))
      (node (ref "U3") (pin "F3") (pinfunction "LDQS_F3") (pintype "passive"))
    )
    (net (code "74") (name "/DQS3_N") (class "Default")
      (node (ref "U1") (pin "W2") (pinfunction "PS_DDR_DQS_N3_502_W2") (pintype "passive"))
      (node (ref "U3") (pin "B7") (pinfunction "~{UDQS}_B7") (pintype "passive"))
    )
    (net (code "75") (name "/DQS3_P") (class "Default")
      (node (ref "U1") (pin "V2") (pinfunction "PS_DDR_DQS_P3_502_V2") (pintype "passive"))
      (node (ref "U3") (pin "C7") (pinfunction "UDQS_C7") (pintype "passive"))
    )
    (net (code "76") (name "/PS_LED") (class "Default")
      (node (ref "U1") (pin "A1") (pinfunction "PS_MIO1_500_A1") (pintype "passive"))
    )
    (net (code "77") (name "/PS_MIO2") (class "Default")
      (node (ref "U1") (pin "A2") (pinfunction "PS_MIO2_500_A2") (pintype "passive"))
    )
    (net (code "78") (name "/PS_MIO3") (class "Default")
      (node (ref "U1") (pin "F6") (pinfunction "PS_MIO3_500_F6") (pintype "passive"))
    )
    (net (code "79") (name "/PS_MIO6") (class "Default")
      (node (ref "U1") (pin "A4") (pinfunction "PS_MIO6_500_A4") (pintype "passive"))
    )
    (net (code "80") (name "/PS_MIO7") (class "Default")
      (node (ref "U1") (pin "D5") (pinfunction "PS_MIO7_500_D5") (pintype "passive"))
    )
    (net (code "81") (name "/PS_MIO8") (class "Default")
      (node (ref "U1") (pin "E5") (pinfunction "PS_MIO8_500_E5") (pintype "passive"))
    )
    (net (code "82") (name "/SD_CD") (class "Default")
      (node (ref "U1") (pin "A6") (pinfunction "PS_MIO13_500_A6") (pintype "passive"))
    )
    (net (code "83") (name "/SD_CMD") (class "Default")
      (node (ref "U1") (pin "C8") (pinfunction "PS_MIO41_501_C8") (pintype "passive"))
    )
    (net (code "84") (name "/SD_D1") (class "Default")
      (node (ref "U1") (pin "B11") (pinfunction "PS_MIO43_501_B11") (pintype "passive"))
    )
    (net (code "85") (name "/SD_D3") (class "Default")
      (node (ref "U1") (pin "B9") (pinfunction "PS_MIO45_501_B9") (pintype "passive"))
    )
    (net (code "86") (name "/SPI1_MISO") (class "Default")
      (node (ref "U1") (pin "B10") (pinfunction "PS_MIO47_501_B10") (pintype "passive"))
    )
    (net (code "87") (name "/USB_D5") (class "Default")
      (node (ref "U1") (pin "B14") (pinfunction "PS_MIO37_501_B14") (pintype "passive"))
    )
    (net (code "88") (name "/USB_D7") (class "Default")
      (node (ref "U1") (pin "C13") (pinfunction "PS_MIO39_501_C13") (pintype "passive"))
    )
    (net (code "89") (name "DDR_VREF") (class "Default")
      (node (ref "C23") (pin "2") (pinfunction "2_2") (pintype "passive"))
      (node (ref "C24") (pin "1") (pinfunction "1_1") (pintype "passive"))
      (node (ref "C25") (pin "2") (pinfunction "2_2") (pintype "passive"))
      (node (ref "C26") (pin "1") (pinfunction "1_1") (pintype "passive"))
      (node (ref "U2") (pin "H1") (pinfunction "VREFDQ_H1") (pintype "passive"))
      (node (ref "U2") (pin "M8") (pinfunction "VREFCA_M8") (pintype "passive"))
      (node (ref "U3") (pin "H1") (pinfunction "VREFDQ_H1") (pintype "passive"))
      (node (ref "U3") (pin "M8") (pinfunction "VREFCA_M8") (pintype "passive"))
    )
    (net (code "90") (name "DDR_VTT") (class "Default")
      (node (ref "C27") (pin "2") (pinfunction "2_2") (pintype "passive"))
      (node (ref "C28") (pin "1") (pinfunction "1_1") (pintype "passive"))
      (node (ref "C29") (pin "1") (pinfunction "1_1") (pintype "passive"))
      (node (ref "C30") (pin "1") (pinfunction "1_1") (pintype "passive"))
      (node (ref "C31") (pin "1") (pinfunction "1_1") (pintype "passive"))
      (node (ref "C32") (pin "1") (pinfunction "1_1") (pintype "passive"))
      (node (ref "C33") (pin "1") (pinfunction "1_1") (pintype "passive"))
      (node (ref "C34") (pin "1") (pinfunction "1_1") (pintype "passive"))
      (node (ref "C35") (pin "1") (pinfunction "1_1") (pintype "passive"))
      (node (ref "C36") (pin "1") (pinfunction "1_1") (pintype "passive"))
      (node (ref "C37") (pin "1") (pinfunction "1_1") (pintype "passive"))
      (node (ref "R10") (pin "1") (pinfunction "1_1") (pintype "passive"))
      (node (ref "R11") (pin "1") (pinfunction "1_1") (pintype "passive"))
      (node (ref "R12") (pin "1") (pinfunction "1_1") (pintype "passive"))
      (node (ref "R13") (pin "1") (pinfunction "1_1") (pintype "passive"))
      (node (ref "R14") (pin "1") (pinfunction "1_1") (pintype "passive"))
      (node (ref "R15") (pin "1") (pinfunction "1_1") (pintype "passive"))
      (node (ref "R16") (pin "1") (pinfunction "1_1") (pintype "passive"))
      (node (ref "R17") (pin "1") (pinfunction "1_1") (pintype "passive"))
      (node (ref "R18") (pin "1") (pinfunction "1_1") (pintype "passive"))
      (node (ref "R19") (pin "1") (pinfunction "1_1") (pintype "passive"))
      (node (ref "R20") (pin "1") (pinfunction "1_1") (pintype "passive"))
      (node (ref "R21") (pin "1") (pinfunction "1_1") (pintype "passive"))
      (node (ref "R22") (pin "1") (pinfunction "1_1") (pintype "passive"))
      (node (ref "R23") (pin "1") (pinfunction "1_1") (pintype "passive"))
      (node (ref "R24") (pin "1") (pinfunction "1_1") (pintype "passive"))
      (node (ref "R25") (pin "1") (pinfunction "1_1") (pintype "passive"))
      (node (ref "R26") (pin "1") (pinfunction "1_1") (pintype "passive"))
      (node (ref "R27") (pin "1") (pinfunction "1_1") (pintype "passive"))
      (node (ref "R28") (pin "1") (pinfunction "1_1") (pintype "passive"))
      (node (ref "R29") (pin "1") (pinfunction "1_1") (pintype "passive"))
      (node (ref "R30") (pin "1") (pinfunction "1_1") (pintype "passive"))
      (node (ref "R7") (pin "1") (pinfunction "1_1") (pintype "passive"))
      (node (ref "R8") (pin "1") (pinfunction "1_1") (pintype "passive"))
      (node (ref "R9") (pin "1") (pinfunction "1_1") (pintype "passive"))
    )
    (net (code "91") (name "GND") (class "Default")
      (node (ref "C1") (pin "1") (pinfunction "1_1") (pintype "passive"))
      (node (ref "C10") (pin "1") (pinfunction "1_1") (pintype "passive"))
      (node (ref "C11") (pin "1") (pinfunction "1_1") (pintype "passive"))
      (node (ref "C12") (pin "1") (pinfunction "1_1") (pintype "passive"))
      (node (ref "C13") (pin "1") (pinfunction "1_1") (pintype "passive"))
      (node (ref "C14") (pin "1") (pinfunction "1_1") (pintype "passive"))
      (node (ref "C15") (pin "1") (pinfunction "1_1") (pintype "passive"))
      (node (ref "C16") (pin "1") (pinfunction "1_1") (pintype "passive"))
      (node (ref "C17") (pin "1") (pinfunction "1_1") (pintype "passive"))
      (node (ref "C18") (pin "1") (pinfunction "1_1") (pintype "passive"))
      (node (ref "C19") (pin "1") (pinfunction "1_1") (pintype "passive"))
      (node (ref "C2") (pin "1") (pinfunction "1_1") (pintype "passive"))
      (node (ref "C20") (pin "1") (pinfunction "1_1") (pintype "passive"))
      (node (ref "C21") (pin "1") (pinfunction "1_1") (pintype "passive"))
      (node (ref "C22") (pin "1") (pinfunction "1_1") (pintype "passive"))
      (node (ref "C23") (pin "1") (pinfunction "1_1") (pintype "passive"))
      (node (ref "C25") (pin "1") (pinfunction "1_1") (pintype "passive"))
      (node (ref "C27") (pin "1") (pinfunction "1_1") (pintype "passive"))
      (node (ref "C28") (pin "2") (pinfunction "2_2") (pintype "passive"))
      (node (ref "C29") (pin "2") (pinfunction "2_2") (pintype "passive"))
      (node (ref "C3") (pin "1") (pinfunction "1_1") (pintype "passive"))
      (node (ref "C30") (pin "2") (pinfunction "2_2") (pintype "passive"))
      (node (ref "C31") (pin "2") (pinfunction "2_2") (pintype "passive"))
      (node (ref "C32") (pin "2") (pinfunction "2_2") (pintype "passive"))
      (node (ref "C33") (pin "2") (pinfunction "2_2") (pintype "passive"))
      (node (ref "C34") (pin "2") (pinfunction "2_2") (pintype "passive"))
      (node (ref "C35") (pin "2") (pinfunction "2_2") (pintype "passive"))
      (node (ref "C36") (pin "2") (pinfunction "2_2") (pintype "passive"))
      (node (ref "C37") (pin "2") (pinfunction "2_2") (pintype "passive"))
      (node (ref "C4") (pin "1") (pinfunction "1_1") (pintype "passive"))
      (node (ref "C5") (pin "1") (pinfunction "1_1") (pintype "passive"))
      (node (ref "C6") (pin "1") (pinfunction "1_1") (pintype "passive"))
      (node (ref "C7") (pin "1") (pinfunction "1_1") (pintype "passive"))
      (node (ref "C8") (pin "1") (pinfunction "1_1") (pintype "passive"))
      (node (ref "C9") (pin "1") (pinfunction "1_1") (pintype "passive"))
      (node (ref "R1") (pin "2") (pinfunction "2_2") (pintype "passive"))
      (node (ref "R2") (pin "2") (pinfunction "2_2") (pintype "passive"))
      (node (ref "R4") (pin "2") (pinfunction "2_2") (pintype "passive"))
      (node (ref "R6") (pin "1") (pinfunction "1_1") (pintype "passive"))
      (node (ref "U2") (pin "A9") (pinfunction "VSS1_A9") (pintype "passive"))
      (node (ref "U2") (pin "B1") (pinfunction "VSSQ1_B1") (pintype "passive"))
      (node (ref "U2") (pin "B3") (pinfunction "VSS2_B3") (pintype "passive"))
      (node (ref "U2") (pin "B9") (pinfunction "VSSQ2_B9") (pintype "passive"))
      (node (ref "U2") (pin "D1") (pinfunction "VSSQ3_D1") (pintype "passive"))
      (node (ref "U2") (pin "D8") (pinfunction "VSSQ4_D8") (pintype "passive"))
      (node (ref "U2") (pin "E1") (pinfunction "VSS3_E1") (pintype "passive"))
      (node (ref "U2") (pin "E2") (pinfunction "VSSQ5_E2") (pintype "passive"))
      (node (ref "U2") (pin "E8") (pinfunction "VSSQ6_E8") (pintype "passive"))
      (node (ref "U2") (pin "F9") (pinfunction "VSSQ7_F9") (pintype "passive"))
      (node (ref "U2") (pin "G1") (pinfunction "VSSQ8_G1") (pintype "passive"))
      (node (ref "U2") (pin "G8") (pinfunction "VSS4_G8") (pintype "passive"))
      (node (ref "U2") (pin "G9") (pinfunction "VSSQ9_G9") (pintype "passive"))
      (node (ref "U2") (pin "J2") (pinfunction "VSS5_J2") (pintype "passive"))
      (node (ref "U2") (pin "J8") (pinfunction "VSS6_J8") (pintype "passive"))
      (node (ref "U2") (pin "M1") (pinfunction "VSS7_M1") (pintype "passive"))
      (node (ref "U2") (pin "M9") (pinfunction "VSS8_M9") (pintype "passive"))
      (node (ref "U2") (pin "P1") (pinfunction "VSS9_P1") (pintype "passive"))
      (node (ref "U2") (pin "P9") (pinfunction "VSS10_P9") (pintype "passive"))
      (node (ref "U2") (pin "T1") (pinfunction "VSS11_T1") (pintype "passive"))
      (node (ref "U2") (pin "T9") (pinfunction "VSS12_T9") (pintype "passive"))
      (node (ref "U3") (pin "A9") (pinfunction "VSS1_A9") (pintype "passive"))
      (node (ref "U3") (pin "B1") (pinfunction "VSSQ1_B1") (pintype "passive"))
      (node (ref "U3") (pin "B3") (pinfunction "VSS2_B3") (pintype "passive"))
      (node (ref "U3") (pin "B9") (pinfunction "VSSQ2_B9") (pintype "passive"))
      (node (ref "U3") (pin "D1") (pinfunction "VSSQ3_D1") (pintype "passive"))
      (node (ref "U3") (pin "D8") (pinfunction "VSSQ4_D8") (pintype "passive"))
      (node (ref "U3") (pin "E1") (pinfunction "VSS3_E1") (pintype "passive"))
      (node (ref "U3") (pin "E2") (pinfunction "VSSQ5_E2") (pintype "passive"))
      (node (ref "U3") (pin "E8") (pinfunction "VSSQ6_E8") (pintype "passive"))
      (node (ref "U3") (pin "F9") (pinfunction "VSSQ7_F9") (pintype "passive"))
      (node (ref "U3") (pin "G1") (pinfunction "VSSQ8_G1") (pintype "passive"))
      (node (ref "U3") (pin "G8") (pinfunction "VSS4_G8") (pintype "passive"))
      (node (ref "U3") (pin "G9") (pinfunction "VSSQ9_G9") (pintype "passive"))
      (node (ref "U3") (pin "J2") (pinfunction "VSS5_J2") (pintype "passive"))
      (node (ref "U3") (pin "J8") (pinfunction "VSS6_J8") (pintype "passive"))
      (node (ref "U3") (pin "M1") (pinfunction "VSS7_M1") (pintype "passive"))
      (node (ref "U3") (pin "M9") (pinfunction "VSS8_M9") (pintype "passive"))
      (node (ref "U3") (pin "P1") (pinfunction "VSS9_P1") (pintype "passive"))
      (node (ref "U3") (pin "P9") (pinfunction "VSS10_P9") (pintype "passive"))
      (node (ref "U3") (pin "T1") (pinfunction "VSS11_T1") (pintype "passive"))
      (node (ref "U3") (pin "T9") (pinfunction "VSS12_T9") (pintype "passive"))
    )
    (net (code "92") (name "Net-(U1C-PS_DDR_VRN_502)") (class "Default")
      (node (ref "R3") (pin "1") (pinfunction "1_1") (pintype "passive"))
      (node (ref "U1") (pin "M7") (pinfunction "PS_DDR_VRN_502_M7") (pintype "passive"))
    )
    (net (code "93") (name "Net-(U1C-PS_DDR_VRP_502)") (class "Default")
      (node (ref "R4") (pin "1") (pinfunction "1_1") (pintype "passive"))
      (node (ref "U1") (pin "N7") (pinfunction "PS_DDR_VRP_502_N7") (pintype "passive"))
    )
    (net (code "94") (name "Net-(U2-ZQ)") (class "Default")
      (node (ref "R1") (pin "1") (pinfunction "1_1") (pintype "passive"))
      (node (ref "U2") (pin "L8") (pinfunction "ZQ_L8") (pintype "passive"))
    )
    (net (code "95") (name "Net-(U3-ZQ)") (class "Default")
      (node (ref "R2") (pin "1") (pinfunction "1_1") (pintype "passive"))
      (node (ref "U3") (pin "L8") (pinfunction "ZQ_L8") (pintype "passive"))
    )
    (net (code "96") (name "VCC_1V35") (class "Default")
      (node (ref "C1") (pin "2") (pinfunction "2_2") (pintype "passive"))
      (node (ref "C10") (pin "2") (pinfunction "2_2") (pintype "passive"))
      (node (ref "C11") (pin "2") (pinfunction "2_2") (pintype "passive"))
      (node (ref "C12") (pin "2") (pinfunction "2_2") (pintype "passive"))
      (node (ref "C13") (pin "2") (pinfunction "2_2") (pintype "passive"))
      (node (ref "C14") (pin "2") (pinfunction "2_2") (pintype "passive"))
      (node (ref "C15") (pin "2") (pinfunction "2_2") (pintype "passive"))
      (node (ref "C16") (pin "2") (pinfunction "2_2") (pintype "passive"))
      (node (ref "C17") (pin "2") (pinfunction "2_2") (pintype "passive"))
      (node (ref "C18") (pin "2") (pinfunction "2_2") (pintype "passive"))
      (node (ref "C19") (pin "2") (pinfunction "2_2") (pintype "passive"))
      (node (ref "C2") (pin "2") (pinfunction "2_2") (pintype "passive"))
      (node (ref "C20") (pin "2") (pinfunction "2_2") (pintype "passive"))
      (node (ref "C21") (pin "2") (pinfunction "2_2") (pintype "passive"))
      (node (ref "C22") (pin "2") (pinfunction "2_2") (pintype "passive"))
      (node (ref "C24") (pin "2") (pinfunction "2_2") (pintype "passive"))
      (node (ref "C26") (pin "2") (pinfunction "2_2") (pintype "passive"))
      (node (ref "C3") (pin "2") (pinfunction "2_2") (pintype "passive"))
      (node (ref "C4") (pin "2") (pinfunction "2_2") (pintype "passive"))
      (node (ref "C5") (pin "2") (pinfunction "2_2") (pintype "passive"))
      (node (ref "C6") (pin "2") (pinfunction "2_2") (pintype "passive"))
      (node (ref "C7") (pin "2") (pinfunction "2_2") (pintype "passive"))
      (node (ref "C8") (pin "2") (pinfunction "2_2") (pintype "passive"))
      (node (ref "C9") (pin "2") (pinfunction "2_2") (pintype "passive"))
      (node (ref "R3") (pin "2") (pinfunction "2_2") (pintype "passive"))
      (node (ref "U2") (pin "A1") (pinfunction "VDDQ1_A1") (pintype "passive"))
      (node (ref "U2") (pin "A8") (pinfunction "VDDQ2_A8") (pintype "passive"))
      (node (ref "U2") (pin "B2") (pinfunction "VDD1_B2") (pintype "passive"))
      (node (ref "U2") (pin "C1") (pinfunction "VDDQ3_C1") (pintype "passive"))
      (node (ref "U2") (pin "C9") (pinfunction "VDDQ4_C9") (pintype "passive"))
      (node (ref "U2") (pin "D2") (pinfunction "VDDQ5_D2") (pintype "passive"))
      (node (ref "U2") (pin "D9") (pinfunction "VDD2_D9") (pintype "passive"))
      (node (ref "U2") (pin "E9") (pinfunction "VDDQ6_E9") (pintype "passive"))
      (node (ref "U2") (pin "F1") (pinfunction "VDDQ7_F1") (pintype "passive"))
      (node (ref "U2") (pin "G7") (pinfunction "VDD3_G7") (pintype "passive"))
      (node (ref "U2") (pin "H2") (pinfunction "VDDQ8_H2") (pintype "passive"))
      (node (ref "U2") (pin "H9") (pinfunction "VDDQ9_H9") (pintype "passive"))
      (node (ref "U2") (pin "K2") (pinfunction "VDD4_K2") (pintype "passive"))
      (node (ref "U2") (pin "K8") (pinfunction "VDD5_K8") (pintype "passive"))
      (node (ref "U2") (pin "N1") (pinfunction "VDD6_N1") (pintype "passive"))
      (node (ref "U2") (pin "N9") (pinfunction "VDD7_N9") (pintype "passive"))
      (node (ref "U2") (pin "R1") (pinfunction "VDD8_R1") (pintype "passive"))
      (node (ref "U2") (pin "R9") (pinfunction "VDD9_R9") (pintype "passive"))
      (node (ref "U3") (pin "A1") (pinfunction "VDDQ1_A1") (pintype "passive"))
      (node (ref "U3") (pin "A8") (pinfunction "VDDQ2_A8") (pintype "passive"))
      (node (ref "U3") (pin "B2") (pinfunction "VDD1_B2") (pintype "passive"))
      (node (ref "U3") (pin "C1") (pinfunction "VDDQ3_C1") (pintype "passive"))
      (node (ref "U3") (pin "C9") (pinfunction "VDDQ4_C9") (pintype "passive"))
      (node (ref "U3") (pin "D2") (pinfunction "VDDQ5_D2") (pintype "passive"))
      (node (ref "U3") (pin "D9") (pinfunction "VDD2_D9") (pintype "passive"))
      (node (ref "U3") (pin "E9") (pinfunction "VDDQ6_E9") (pintype "passive"))
      (node (ref "U3") (pin "F1") (pinfunction "VDDQ7_F1") (pintype "passive"))
      (node (ref "U3") (pin "G7") (pinfunction "VDD3_G7") (pintype "passive"))
      (node (ref "U3") (pin "H2") (pinfunction "VDDQ8_H2") (pintype "passive"))
      (node (ref "U3") (pin "H9") (pinfunction "VDDQ9_H9") (pintype "passive"))
      (node (ref "U3") (pin "K2") (pinfunction "VDD4_K2") (pintype "passive"))
      (node (ref "U3") (pin "K8") (pinfunction "VDD5_K8") (pintype "passive"))
      (node (ref "U3") (pin "N1") (pinfunction "VDD6_N1") (pintype "passive"))
      (node (ref "U3") (pin "N9") (pinfunction "VDD7_N9") (pintype "passive"))
      (node (ref "U3") (pin "R1") (pinfunction "VDD8_R1") (pintype "passive"))
      (node (ref "U3") (pin "R9") (pinfunction "VDD9_R9") (pintype "passive"))
    )
    (net (code "97") (name "unconnected-(U1C-PS_MIO0_500-PadG6)") (class "Default")
      (node (ref "U1") (pin "G6") (pinfunction "PS_MIO0_500_G6") (pintype "passive"))
    )
    (net (code "98") (name "unconnected-(U1C-PS_MIO9_500-PadC4)") (class "Default")
      (node (ref "U1") (pin "C4") (pinfunction "PS_MIO9_500_C4") (pintype "passive"))
    )
    (net (code "99") (name "unconnected-(U1C-PS_MIO12_500-PadC5)") (class "Default")
      (node (ref "U1") (pin "C5") (pinfunction "PS_MIO12_500_C5") (pintype "passive"))
    )
    (net (code "100") (name "unconnected-(U1C-PS_MIO49_501-PadC14)") (class "Default")
      (node (ref "U1") (pin "C14") (pinfunction "PS_MIO49_501_C14") (pintype "passive"))
    )
    (net (code "101") (name "unconnected-(U1C-PS_MIO51_501-PadC10)") (class "Default")
      (node (ref "U1") (pin "C10") (pinfunction "PS_MIO51_501_C10") (pintype "passive"))
    )
    (net (code "102") (name "unconnected-(U1C-PS_MIO53_501-PadC12)") (class "Default")
      (node (ref "U1") (pin "C12") (pinfunction "PS_MIO53_501_C12") (pintype "passive"))
    )
    (net (code "103") (name "unconnected-(U2-NC_J1-PadJ1)") (class "Default")
      (node (ref "U2") (pin "J1") (pinfunction "NC_J1_J1") (pintype "passive+no_connect"))
    )
    (net (code "104") (name "unconnected-(U2-NC_J9-PadJ9)") (class "Default")
      (node (ref "U2") (pin "J9") (pinfunction "NC_J9_J9") (pintype "passive+no_connect"))
    )
    (net (code "105") (name "unconnected-(U2-NC_L1-PadL1)") (class "Default")
      (node (ref "U2") (pin "L1") (pinfunction "NC_L1_L1") (pintype "passive+no_connect"))
    )
    (net (code "106") (name "unconnected-(U2-NC_L9-PadL9)") (class "Default")
      (node (ref "U2") (pin "L9") (pinfunction "NC_L9_L9") (pintype "passive+no_connect"))
    )
    (net (code "107") (name "unconnected-(U2-NC_M7-PadM7)") (class "Default")
      (node (ref "U2") (pin "M7") (pinfunction "NC_M7_M7") (pintype "passive+no_connect"))
    )
    (net (code "108") (name "unconnected-(U3-NC_J1-PadJ1)") (class "Default")
      (node (ref "U3") (pin "J1") (pinfunction "NC_J1_J1") (pintype "passive+no_connect"))
    )
    (net (code "109") (name "unconnected-(U3-NC_J9-PadJ9)") (class "Default")
      (node (ref "U3") (pin "J9") (pinfunction "NC_J9_J9") (pintype "passive+no_connect"))
    )
    (net (code "110") (name "unconnected-(U3-NC_L1-PadL1)") (class "Default")
      (node (ref "U3") (pin "L1") (pinfunction "NC_L1_L1") (pintype "passive+no_connect"))
    )
    (net (code "111") (name "unconnected-(U3-NC_L9-PadL9)") (class "Default")
      (node (ref "U3") (pin "L9") (pinfunction "NC_L9_L9") (pintype "passive+no_connect"))
    )
    (net (code "112") (name "unconnected-(U3-NC_M7-PadM7)") (class "Default")
      (node (ref "U3") (pin "M7") (pinfunction "NC_M7_M7") (pintype "passive+no_connect"))
    )
  )
)
